# Ausgangsverst_rker_50_Ohm.net
KiCad netlist of a schematic drawn in EAGLE
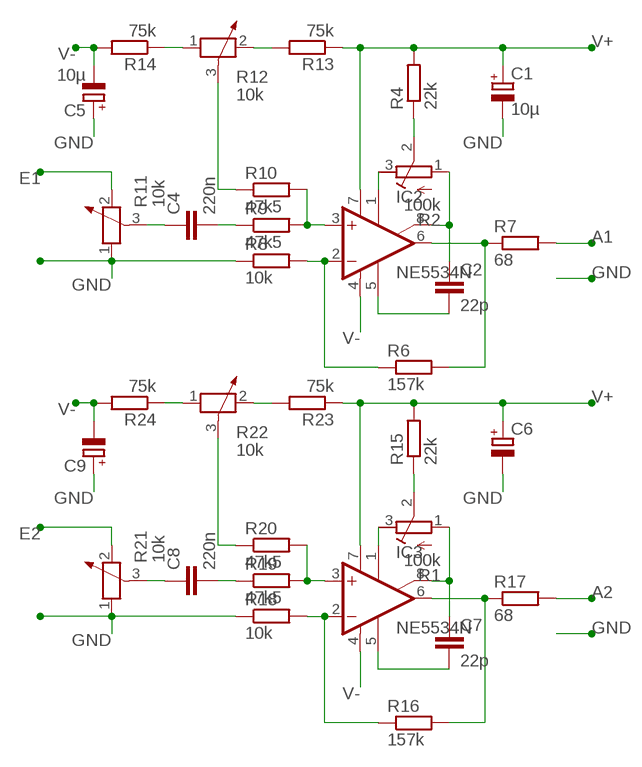
[diagram p0: schematic, sheet 1]

(export (version "E")
  (design (tool "Eeschema 10.0.6"))
  (components
    (comp (ref "C1")
      (value "10µ")
      (footprint "eagle-import:E2-5")
      (libsource (lib "eagle-import") (part "CPOL-EUE2-5"))
    )
    (comp (ref "C2")
      (value "22p")
      (footprint "eagle-import:C050-024X044")
      (libsource (lib "eagle-import") (part "C-EU050-024X044"))
    )
    (comp (ref "C4")
      (value "220n")
      (footprint "eagle-import:C050-024X044")
      (libsource (lib "eagle-import") (part "C-EU050-024X044"))
    )
    (comp (ref "C5")
      (value "10µ")
      (footprint "eagle-import:E2-5")
      (libsource (lib "eagle-import") (part "CPOL-EUE2-5"))
    )
    (comp (ref "C6")
      (value "CPOL-EUE2-5")
      (footprint "eagle-import:E2-5")
      (libsource (lib "eagle-import") (part "CPOL-EUE2-5"))
    )
    (comp (ref "C7")
      (value "22p")
      (footprint "eagle-import:C050-024X044")
      (libsource (lib "eagle-import") (part "C-EU050-024X044"))
    )
    (comp (ref "C8")
      (value "220n")
      (footprint "eagle-import:C050-024X044")
      (libsource (lib "eagle-import") (part "C-EU050-024X044"))
    )
    (comp (ref "C9")
      (value "CPOL-EUE2-5")
      (footprint "eagle-import:E2-5")
      (libsource (lib "eagle-import") (part "CPOL-EUE2-5"))
    )
    (comp (ref "IC2")
      (value "NE5534N")
      (footprint "eagle-import:DIL08")
      (libsource (lib "eagle-import") (part "NE5534N"))
    )
    (comp (ref "IC3")
      (value "NE5534N")
      (footprint "eagle-import:DIL08")
      (libsource (lib "eagle-import") (part "NE5534N"))
    )
    (comp (ref "R1")
      (value "100k")
      (footprint "eagle-import:RTRIM64W")
      (libsource (lib "eagle-import") (part "R-TRIMM64W"))
    )
    (comp (ref "R2")
      (value "100k")
      (footprint "eagle-import:RTRIM64W")
      (libsource (lib "eagle-import") (part "R-TRIMM64W"))
    )
    (comp (ref "R4")
      (value "22k")
      (footprint "eagle-import:0207_12")
      (libsource (lib "eagle-import") (part "R-EU_0207/12"))
    )
    (comp (ref "R6")
      (value "157k")
      (footprint "eagle-import:0207_12")
      (libsource (lib "eagle-import") (part "R-EU_0207/12"))
    )
    (comp (ref "R7")
      (value "68")
      (footprint "eagle-import:0207_12")
      (libsource (lib "eagle-import") (part "R-EU_0207/12"))
    )
    (comp (ref "R8")
      (value "10k")
      (footprint "eagle-import:0207_12")
      (libsource (lib "eagle-import") (part "R-EU_0207/12"))
    )
    (comp (ref "R9")
      (value "47k5")
      (footprint "eagle-import:0207_12")
      (libsource (lib "eagle-import") (part "R-EU_0207/12"))
    )
    (comp (ref "R10")
      (value "47k5")
      (footprint "eagle-import:0207_12")
      (libsource (lib "eagle-import") (part "R-EU_0207/12"))
    )
    (comp (ref "R11")
      (value "10k")
      (footprint "eagle-import:PT-10")
      (libsource (lib "eagle-import") (part "POTENTIOMETER_PT-10"))
    )
    (comp (ref "R12")
      (value "10k")
      (footprint "eagle-import:PT-10")
      (libsource (lib "eagle-import") (part "POTENTIOMETER_PT-10"))
    )
    (comp (ref "R13")
      (value "75k")
      (footprint "eagle-import:0207_12")
      (libsource (lib "eagle-import") (part "R-EU_0207/12"))
    )
    (comp (ref "R14")
      (value "75k")
      (footprint "eagle-import:0207_12")
      (libsource (lib "eagle-import") (part "R-EU_0207/12"))
    )
    (comp (ref "R15")
      (value "22k")
      (footprint "eagle-import:0207_12")
      (libsource (lib "eagle-import") (part "R-EU_0207/12"))
    )
    (comp (ref "R16")
      (value "157k")
      (footprint "eagle-import:0207_12")
      (libsource (lib "eagle-import") (part "R-EU_0207/12"))
    )
    (comp (ref "R17")
      (value "68")
      (footprint "eagle-import:0207_12")
      (libsource (lib "eagle-import") (part "R-EU_0207/12"))
    )
    (comp (ref "R18")
      (value "10k")
      (footprint "eagle-import:0207_12")
      (libsource (lib "eagle-import") (part "R-EU_0207/12"))
    )
    (comp (ref "R19")
      (value "47k5")
      (footprint "eagle-import:0207_12")
      (libsource (lib "eagle-import") (part "R-EU_0207/12"))
    )
    (comp (ref "R20")
      (value "47k5")
      (footprint "eagle-import:0207_12")
      (libsource (lib "eagle-import") (part "R-EU_0207/12"))
    )
    (comp (ref "R21")
      (value "10k")
      (footprint "eagle-import:PT-10")
      (libsource (lib "eagle-import") (part "POTENTIOMETER_PT-10"))
    )
    (comp (ref "R22")
      (value "10k")
      (footprint "eagle-import:PT-10")
      (libsource (lib "eagle-import") (part "POTENTIOMETER_PT-10"))
    )
    (comp (ref "R23")
      (value "75k")
      (footprint "eagle-import:0207_12")
      (libsource (lib "eagle-import") (part "R-EU_0207/12"))
    )
    (comp (ref "R24")
      (value "75k")
      (footprint "eagle-import:0207_12")
      (libsource (lib "eagle-import") (part "R-EU_0207/12"))
    )
  )
  (nets
    (net (code "1") (name "/A1") (class "Default")
      (node (ref "R7") (pin "2") (pinfunction "2_2") (pintype "passive"))
    )
    (net (code "2") (name "/A2") (class "Default")
      (node (ref "R17") (pin "2") (pinfunction "2_2") (pintype "passive"))
    )
    (net (code "3") (name "/E1") (class "Default")
      (node (ref "R11") (pin "2") (pinfunction "2_2") (pintype "passive"))
    )
    (net (code "4") (name "/E2") (class "Default")
      (node (ref "R21") (pin "2") (pinfunction "2_2") (pintype "passive"))
    )
    (net (code "5") (name "/GND") (class "Default")
      (node (ref "C1") (pin "-") (pinfunction "-_-") (pintype "passive"))
      (node (ref "C5") (pin "+") (pinfunction "+_+") (pintype "passive"))
      (node (ref "C6") (pin "-") (pinfunction "-_-") (pintype "passive"))
      (node (ref "C9") (pin "+") (pinfunction "+_+") (pintype "passive"))
      (node (ref "R11") (pin "1") (pinfunction "1_1") (pintype "passive"))
      (node (ref "R18") (pin "1") (pinfunction "1_1") (pintype "passive"))
      (node (ref "R21") (pin "1") (pinfunction "1_1") (pintype "passive"))
      (node (ref "R8") (pin "1") (pinfunction "1_1") (pintype "passive"))
    )
    (net (code "6") (name "/V+") (class "Default")
      (node (ref "C1") (pin "+") (pinfunction "+_+") (pintype "passive"))
      (node (ref "C6") (pin "+") (pinfunction "+_+") (pintype "passive"))
      (node (ref "IC2") (pin "7") (pinfunction "V+_7") (pintype "power_in"))
      (node (ref "IC3") (pin "7") (pinfunction "V+_7") (pintype "power_in"))
      (node (ref "R13") (pin "1") (pinfunction "1_1") (pintype "passive"))
      (node (ref "R15") (pin "2") (pinfunction "2_2") (pintype "passive"))
      (node (ref "R23") (pin "1") (pinfunction "1_1") (pintype "passive"))
      (node (ref "R4") (pin "2") (pinfunction "2_2") (pintype "passive"))
    )
    (net (code "7") (name "/V-") (class "Default")
      (node (ref "C5") (pin "-") (pinfunction "-_-") (pintype "passive"))
      (node (ref "C9") (pin "-") (pinfunction "-_-") (pintype "passive"))
      (node (ref "IC2") (pin "4") (pinfunction "V-_4") (pintype "power_in"))
      (node (ref "IC3") (pin "4") (pinfunction "V-_4") (pintype "power_in"))
      (node (ref "R14") (pin "2") (pinfunction "2_2") (pintype "passive"))
      (node (ref "R24") (pin "2") (pinfunction "2_2") (pintype "passive"))
    )
    (net (code "8") (name "Net-(C4-Pad1)") (class "Default")
      (node (ref "C4") (pin "1") (pinfunction "1_1") (pintype "passive"))
      (node (ref "R11") (pin "3") (pinfunction "3_3") (pintype "passive"))
    )
    (net (code "9") (name "Net-(C4-Pad2)") (class "Default")
      (node (ref "C4") (pin "2") (pinfunction "2_2") (pintype "passive"))
      (node (ref "R9") (pin "1") (pinfunction "1_1") (pintype "passive"))
    )
    (net (code "10") (name "Net-(C8-Pad1)") (class "Default")
      (node (ref "C8") (pin "1") (pinfunction "1_1") (pintype "passive"))
      (node (ref "R21") (pin "3") (pinfunction "3_3") (pintype "passive"))
    )
    (net (code "11") (name "Net-(C8-Pad2)") (class "Default")
      (node (ref "C8") (pin "2") (pinfunction "2_2") (pintype "passive"))
      (node (ref "R19") (pin "1") (pinfunction "1_1") (pintype "passive"))
    )
    (net (code "12") (name "Net-(IC2-+IN)") (class "Default")
      (node (ref "IC2") (pin "3") (pinfunction "+IN_3") (pintype "input"))
      (node (ref "R10") (pin "2") (pinfunction "2_2") (pintype "passive"))
      (node (ref "R9") (pin "2") (pinfunction "2_2") (pintype "passive"))
    )
    (net (code "13") (name "Net-(IC2--IN)") (class "Default")
      (node (ref "IC2") (pin "2") (pinfunction "-IN_2") (pintype "input"))
      (node (ref "R6") (pin "1") (pinfunction "1_1") (pintype "passive"))
      (node (ref "R8") (pin "2") (pinfunction "2_2") (pintype "passive"))
    )
    (net (code "14") (name "Net-(IC2-CMP)") (class "Default")
      (node (ref "C2") (pin "2") (pinfunction "2_2") (pintype "passive"))
      (node (ref "IC2") (pin "5") (pinfunction "CMP_5") (pintype "passive"))
    )
    (net (code "15") (name "Net-(IC2-ON)") (class "Default")
      (node (ref "IC2") (pin "1") (pinfunction "ON_1") (pintype "passive"))
      (node (ref "R2") (pin "3") (pinfunction "E_3") (pintype "passive"))
    )
    (net (code "16") (name "Net-(IC2-ON{slash}CMP)") (class "Default")
      (node (ref "C2") (pin "1") (pinfunction "1_1") (pintype "passive"))
      (node (ref "IC2") (pin "8") (pinfunction "ON/CMP_8") (pintype "passive"))
      (node (ref "R2") (pin "1") (pinfunction "A_1") (pintype "passive"))
    )
    (net (code "17") (name "Net-(IC2-OUT)") (class "Default")
      (node (ref "IC2") (pin "6") (pinfunction "OUT_6") (pintype "output"))
      (node (ref "R6") (pin "2") (pinfunction "2_2") (pintype "passive"))
      (node (ref "R7") (pin "1") (pinfunction "1_1") (pintype "passive"))
    )
    (net (code "18") (name "Net-(IC3-+IN)") (class "Default")
      (node (ref "IC3") (pin "3") (pinfunction "+IN_3") (pintype "input"))
      (node (ref "R19") (pin "2") (pinfunction "2_2") (pintype "passive"))
      (node (ref "R20") (pin "2") (pinfunction "2_2") (pintype "passive"))
    )
    (net (code "19") (name "Net-(IC3--IN)") (class "Default")
      (node (ref "IC3") (pin "2") (pinfunction "-IN_2") (pintype "input"))
      (node (ref "R16") (pin "1") (pinfunction "1_1") (pintype "passive"))
      (node (ref "R18") (pin "2") (pinfunction "2_2") (pintype "passive"))
    )
    (net (code "20") (name "Net-(IC3-CMP)") (class "Default")
      (node (ref "C7") (pin "2") (pinfunction "2_2") (pintype "passive"))
      (node (ref "IC3") (pin "5") (pinfunction "CMP_5") (pintype "passive"))
    )
    (net (code "21") (name "Net-(IC3-ON)") (class "Default")
      (node (ref "IC3") (pin "1") (pinfunction "ON_1") (pintype "passive"))
      (node (ref "R1") (pin "3") (pinfunction "E_3") (pintype "passive"))
    )
    (net (code "22") (name "Net-(IC3-ON{slash}CMP)") (class "Default")
      (node (ref "C7") (pin "1") (pinfunction "1_1") (pintype "passive"))
      (node (ref "IC3") (pin "8") (pinfunction "ON/CMP_8") (pintype "passive"))
      (node (ref "R1") (pin "1") (pinfunction "A_1") (pintype "passive"))
    )
    (net (code "23") (name "Net-(IC3-OUT)") (class "Default")
      (node (ref "IC3") (pin "6") (pinfunction "OUT_6") (pintype "output"))
      (node (ref "R16") (pin "2") (pinfunction "2_2") (pintype "passive"))
      (node (ref "R17") (pin "1") (pinfunction "1_1") (pintype "passive"))
    )
    (net (code "24") (name "Net-(R1-S)") (class "Default")
      (node (ref "R1") (pin "2") (pinfunction "S_2") (pintype "passive"))
      (node (ref "R15") (pin "1") (pinfunction "1_1") (pintype "passive"))
    )
    (net (code "25") (name "Net-(R2-S)") (class "Default")
      (node (ref "R2") (pin "2") (pinfunction "S_2") (pintype "passive"))
      (node (ref "R4") (pin "1") (pinfunction "1_1") (pintype "passive"))
    )
    (net (code "26") (name "Net-(R10-Pad1)") (class "Default")
      (node (ref "R10") (pin "1") (pinfunction "1_1") (pintype "passive"))
      (node (ref "R12") (pin "3") (pinfunction "3_3") (pintype "passive"))
    )
    (net (code "27") (name "Net-(R12-Pad1)") (class "Default")
      (node (ref "R12") (pin "1") (pinfunction "1_1") (pintype "passive"))
      (node (ref "R14") (pin "1") (pinfunction "1_1") (pintype "passive"))
    )
    (net (code "28") (name "Net-(R12-Pad2)") (class "Default")
      (node (ref "R12") (pin "2") (pinfunction "2_2") (pintype "passive"))
      (node (ref "R13") (pin "2") (pinfunction "2_2") (pintype "passive"))
    )
    (net (code "29") (name "Net-(R20-Pad1)") (class "Default")
      (node (ref "R20") (pin "1") (pinfunction "1_1") (pintype "passive"))
      (node (ref "R22") (pin "3") (pinfunction "3_3") (pintype "passive"))
    )
    (net (code "30") (name "Net-(R22-Pad1)") (class "Default")
      (node (ref "R22") (pin "1") (pinfunction "1_1") (pintype "passive"))
      (node (ref "R24") (pin "1") (pinfunction "1_1") (pintype "passive"))
    )
    (net (code "31") (name "Net-(R22-Pad2)") (class "Default")
      (node (ref "R22") (pin "2") (pinfunction "2_2") (pintype "passive"))
      (node (ref "R23") (pin "2") (pinfunction "2_2") (pintype "passive"))
    )
  )
)
